# ProProject_my_heart_2023-08-05.net
KiCad netlist of a schematic drawn in EasyEDA Pro
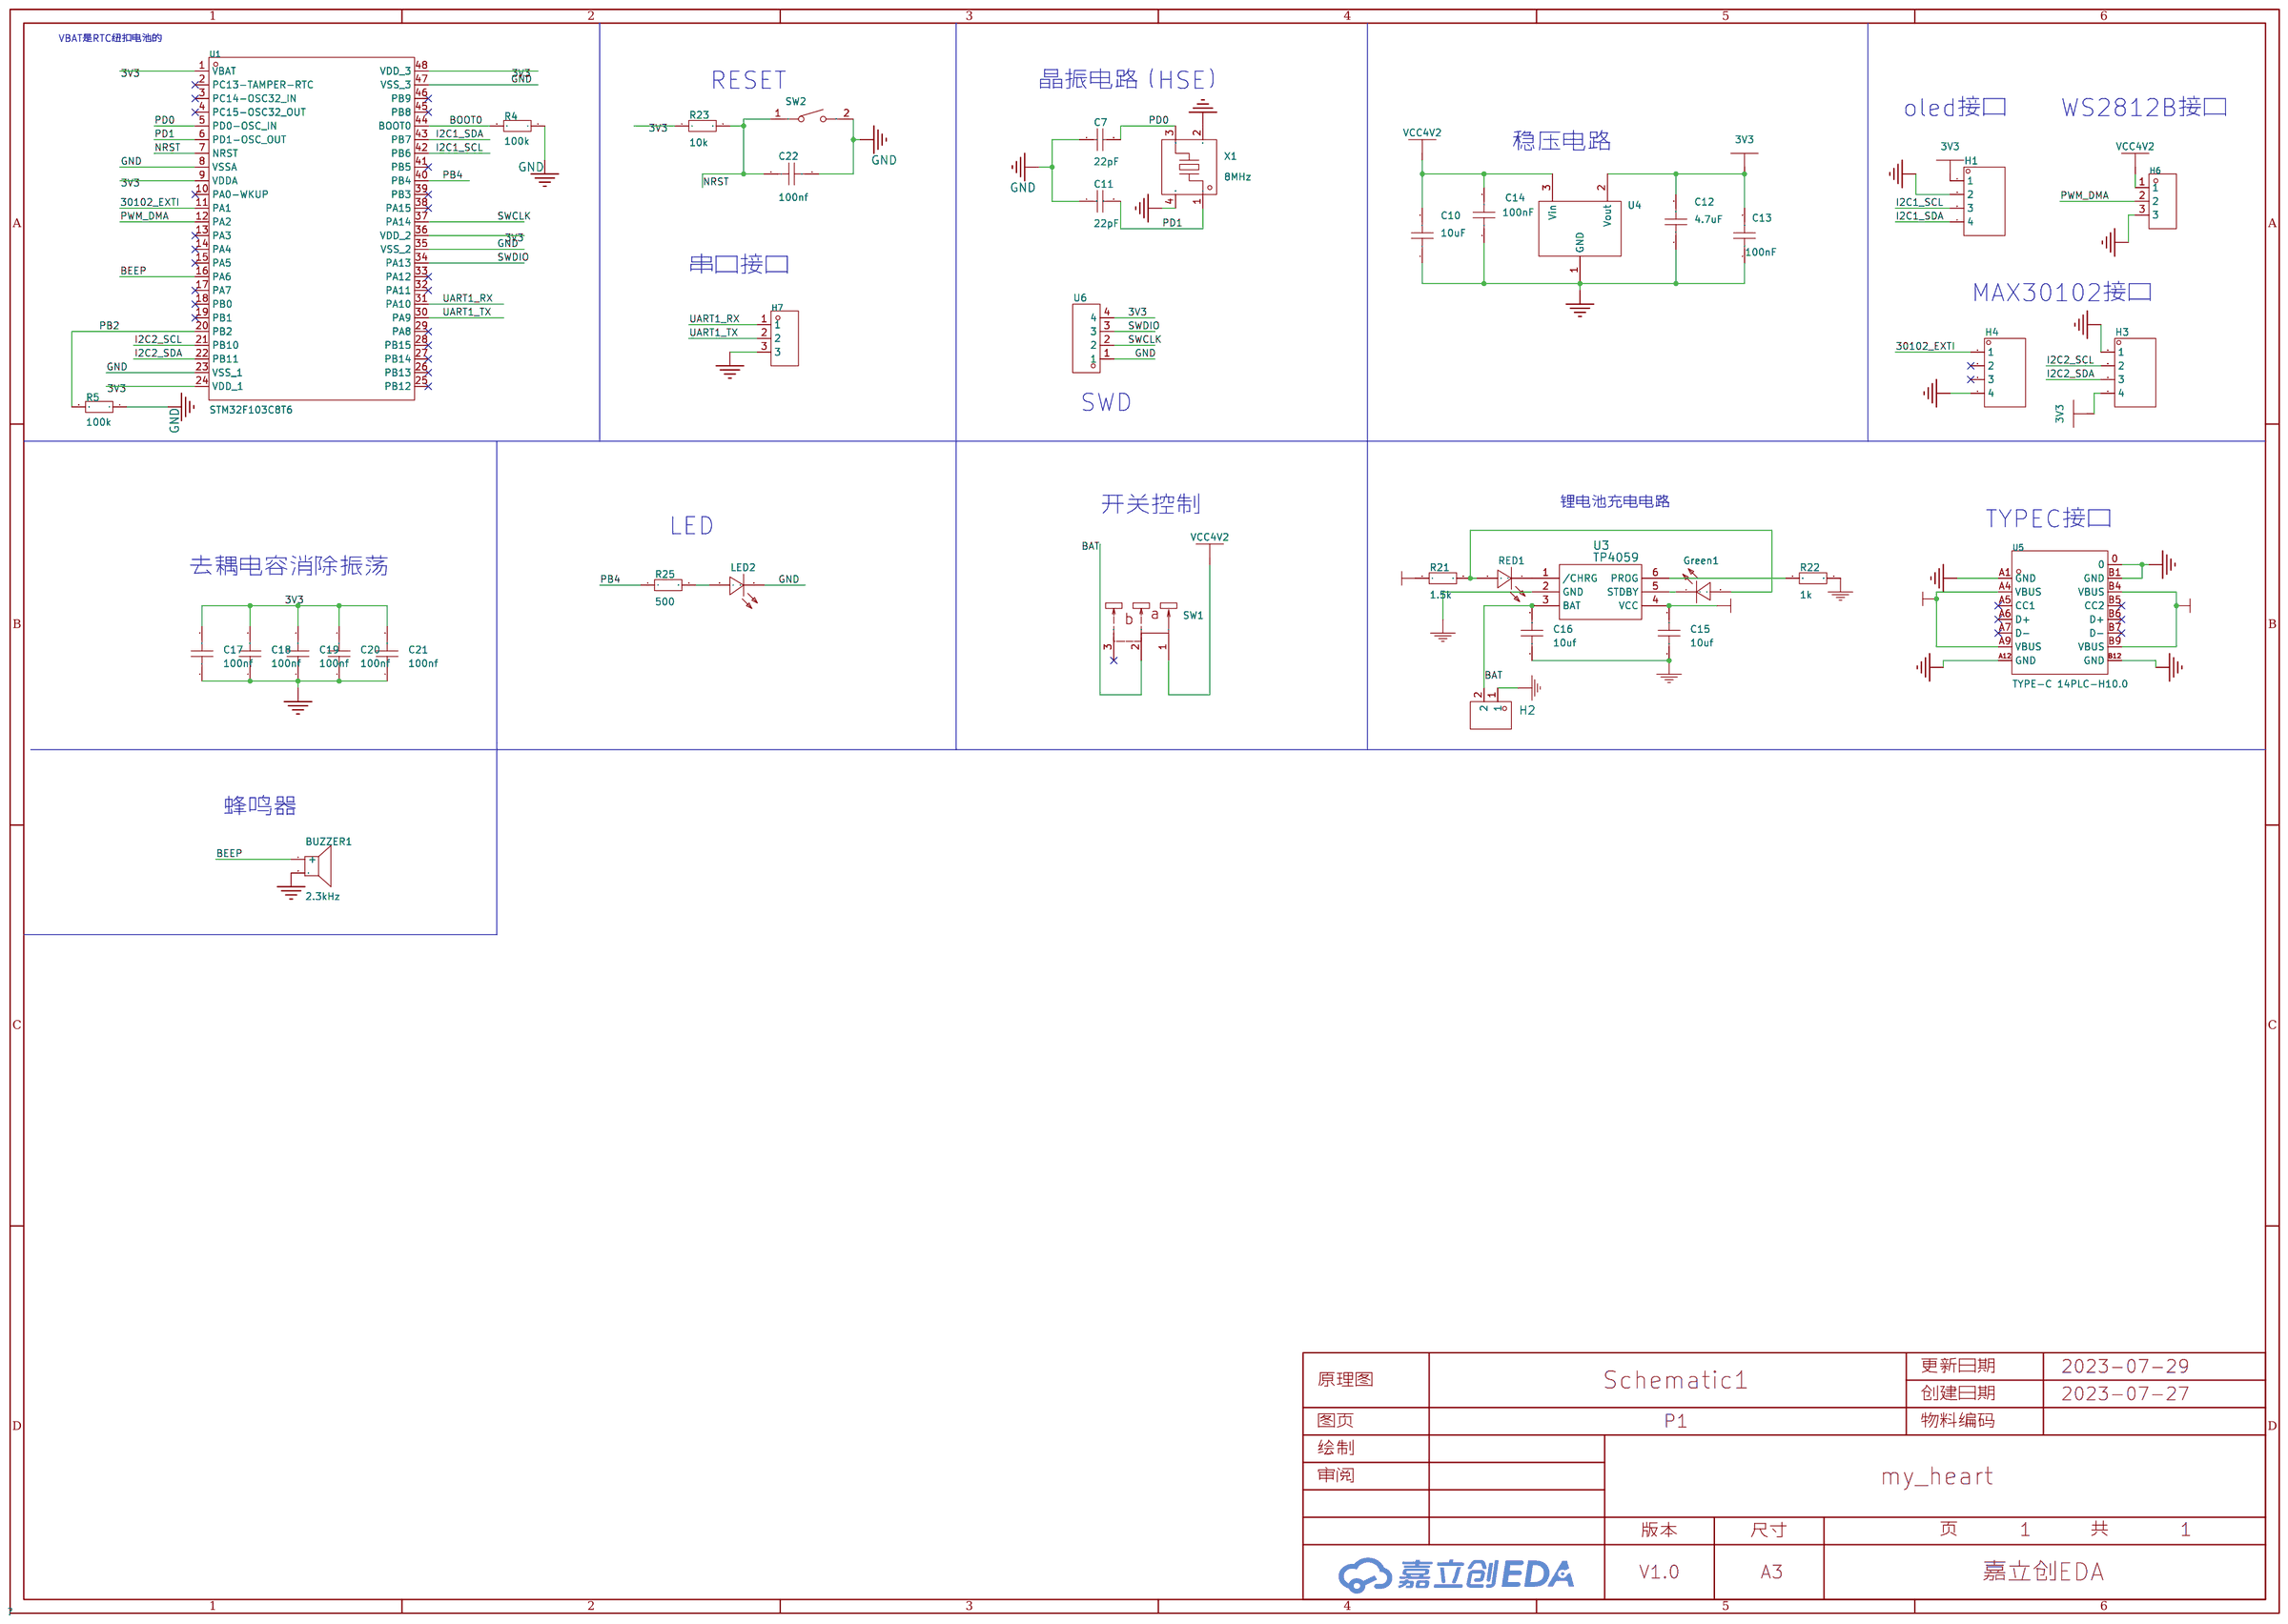
[diagram p0: schematic sheet]

(export (version "E")
  (design (tool "Eeschema 10.0.6"))
  (components
    (comp (ref "BUZZER1")
      (value "2.3kHz")
      (footprint "easyedapro:BUZ-TH_BD12.0-P7.60-D0.6-FD")
      (description "驱动方式:有源(内含驱动线路);构造类型:电磁式;额定电压:5V;频率:2.3kHz;声压(SPL):85dB@5V,10cm;")
      (fields (field (name "Manufacturer Part") "TMB12A05") (field (name "Manufacturer") "华能"))
      (libsource (lib "easyedapro") (part "TMB12A05"))
    )
    (comp (ref "C7")
      (value "22pF")
      (footprint "easyedapro:C0805")
      (description "容值:22pF;精度:±5%;额定电压:50V;温度系数:NP0;")
      (fields
        (field (name "Manufacturer Part") "CC0805JRNPO9BN220")
        (field (name "Manufacturer") "YAGEO(国巨)")
      )
      (libsource (lib "easyedapro") (part "CC0805JRNPO9BN220"))
    )
    (comp (ref "C10")
      (value "10uF")
      (footprint "easyedapro:c0805")
      (description "容值:10uF;精度:±10%;额定电压:16V;温度系数:X7R;")
      (fields
        (field (name "Manufacturer Part") "CL21B106KOQNNNE")
        (field (name "Manufacturer") "SAMSUNG(三星)")
      )
      (libsource (lib "easyedapro") (part "CL21B106KOQNNNE"))
    )
    (comp (ref "C11")
      (value "22pF")
      (footprint "easyedapro:C0805")
      (description "容值:22pF;精度:±5%;额定电压:50V;温度系数:NP0;")
      (fields
        (field (name "Manufacturer Part") "CC0805JRNPO9BN220")
        (field (name "Manufacturer") "YAGEO(国巨)")
      )
      (libsource (lib "easyedapro") (part "CC0805JRNPO9BN220"))
    )
    (comp (ref "C12")
      (value "4.7uF")
      (footprint "easyedapro:c0805")
      (description "容值:4.7uF;精度:±10%;额定电压:25V;温度系数:X5R;")
      (fields
        (field (name "Manufacturer Part") "CC0805KKX5R8BB475")
        (field (name "Manufacturer") "YAGEO(国巨)")
      )
      (libsource (lib "easyedapro") (part "CC0805KKX5R8BB475"))
    )
    (comp (ref "C13")
      (value "100nF")
      (footprint "easyedapro:c0805")
      (description "容值:100nF;精度:±10%;额定电压:25V;温度系数:X7R;")
      (fields
        (field (name "Manufacturer Part") "TCC0805X7R104K250DTS")
        (field (name "Manufacturer") "CCTC(三环)")
      )
      (libsource (lib "easyedapro") (part "TCC0805X7R104K250DTS"))
    )
    (comp (ref "C14")
      (value "100nF")
      (footprint "easyedapro:c0805")
      (description "容值:100nF;精度:±10%;额定电压:25V;温度系数:X7R;")
      (fields
        (field (name "Manufacturer Part") "TCC0805X7R104K250DTS")
        (field (name "Manufacturer") "CCTC(三环)")
      )
      (libsource (lib "easyedapro") (part "TCC0805X7R104K250DTS"))
    )
    (comp (ref "C15")
      (value "100nF")
      (footprint "easyedapro:C0603")
      (libsource (lib "easyedapro") (part "CapAcitance"))
    )
    (comp (ref "C16")
      (value "100nF")
      (footprint "easyedapro:C0603")
      (libsource (lib "easyedapro") (part "CapAcitance"))
    )
    (comp (ref "C17")
      (value "100nF")
      (footprint "easyedapro:C0603")
      (libsource (lib "easyedapro") (part "CapAcitance"))
    )
    (comp (ref "C18")
      (value "100nF")
      (footprint "easyedapro:C0603")
      (libsource (lib "easyedapro") (part "CapAcitance"))
    )
    (comp (ref "C19")
      (value "100nF")
      (footprint "easyedapro:C0603")
      (libsource (lib "easyedapro") (part "CapAcitance"))
    )
    (comp (ref "C20")
      (value "100nF")
      (footprint "easyedapro:C0603")
      (libsource (lib "easyedapro") (part "CapAcitance"))
    )
    (comp (ref "C21")
      (value "100nF")
      (footprint "easyedapro:C0603")
      (libsource (lib "easyedapro") (part "CapAcitance"))
    )
    (comp (ref "C22")
      (value "100nF")
      (footprint "easyedapro:C0603")
      (libsource (lib "easyedapro") (part "CapAcitance"))
    )
    (comp (ref "Green1")
      (value "KT-0603R")
      (footprint "easyedapro:LED0603-RD")
      (description "发光颜色:红灯;二极管配置:-;透镜颜色:-;主波长:-;色温:-;功率:-;发光角度:-;安装方式:-;工作温度:-40°C~+85°C;")
      (fields (field (name "Manufacturer") "KENTO"))
      (libsource (lib "easyedapro") (part "KT-0603R"))
    )
    (comp (ref "H1")
      (value "~")
      (footprint "easyedapro:HDR-TH_4P-P2.54-V-M_1")
      (fields (field (name "Manufacturer Part") "B-2100S04P-A110") (field (name "Manufacturer") "Ckmtw(灿科盟)"))
      (libsource (lib "easyedapro") (part "Header-Male-2.54_1x4"))
    )
    (comp (ref "H2")
      (value "MF254V-11-02-0743")
      (footprint "easyedapro:HDR-TH_2P-P2.00-V-M")
      (fields (field (name "Manufacturer") "XFCN(台湾兴飞)"))
      (libsource (lib "easyedapro") (part "MF254V-11-02-0743"))
    )
    (comp (ref "H3")
      (value "~")
      (footprint "easyedapro:HDR-TH_4P-P2.54-V-M_1")
      (fields (field (name "Manufacturer Part") "B-2100S04P-A110") (field (name "Manufacturer") "Ckmtw(灿科盟)"))
      (libsource (lib "easyedapro") (part "Header-Male-2.54_1x4"))
    )
    (comp (ref "H4")
      (value "~")
      (footprint "easyedapro:HDR-TH_4P-P2.54-V-M_1")
      (fields (field (name "Manufacturer Part") "B-2100S04P-A110") (field (name "Manufacturer") "Ckmtw(灿科盟)"))
      (libsource (lib "easyedapro") (part "Header-Male-2.54_1x4"))
    )
    (comp (ref "H6")
      (value "~")
      (footprint "easyedapro:HDR-TH_3P-P2.54-V-F")
      (libsource (lib "easyedapro") (part "PM254V-11-03-H85"))
    )
    (comp (ref "H7")
      (value "~")
      (footprint "easyedapro:HDR-TH_3P-P2.54-V-F")
      (libsource (lib "easyedapro") (part "PM254V-11-03-H85"))
    )
    (comp (ref "LED2")
      (value "KT-0603R")
      (footprint "easyedapro:LED0603-RD")
      (description "发光颜色:红灯;二极管配置:-;透镜颜色:-;主波长:-;色温:-;功率:-;发光角度:-;安装方式:-;工作温度:-40°C~+85°C;")
      (fields (field (name "Manufacturer") "KENTO"))
      (libsource (lib "easyedapro") (part "KT-0603R"))
    )
    (comp (ref "R4")
      (value "100k")
      (footprint "easyedapro:R0201")
      (description "阻值:10k;精度:±1%;功率:50mW;温度系数:±200ppm/;最大工作电压:25V;工作温度范围:-55~+125;")
      (fields (field (name "Manufacturer Part") "RC-01W1002FT") (field (name "Manufacturer") "FH(风华)"))
      (libsource (lib "easyedapro") (part "RC-01W1002FT"))
    )
    (comp (ref "R5")
      (value "100k")
      (footprint "easyedapro:R0201")
      (description "阻值:10k;精度:±1%;功率:50mW;温度系数:±200ppm/;最大工作电压:25V;工作温度范围:-55~+125;")
      (fields (field (name "Manufacturer Part") "RC-01W1002FT") (field (name "Manufacturer") "FH(风华)"))
      (libsource (lib "easyedapro") (part "RC-01W1002FT"))
    )
    (comp (ref "R21") (value "10K") (footprint "easyedapro:R0603") (libsource (lib "easyedapro") (part "电阻")))
    (comp (ref "R22") (value "10K") (footprint "easyedapro:R0603") (libsource (lib "easyedapro") (part "电阻")))
    (comp (ref "R23") (value "10K") (footprint "easyedapro:R0603") (libsource (lib "easyedapro") (part "电阻")))
    (comp (ref "R25") (value "10K") (footprint "easyedapro:R0603") (libsource (lib "easyedapro") (part "电阻")))
    (comp (ref "RED1")
      (value "KT-0603R")
      (footprint "easyedapro:LED0603-RD")
      (description "发光颜色:红灯;二极管配置:-;透镜颜色:-;主波长:-;色温:-;功率:-;发光角度:-;安装方式:-;工作温度:-40°C~+85°C;")
      (fields (field (name "Manufacturer") "KENTO"))
      (libsource (lib "easyedapro") (part "KT-0603R"))
    )
    (comp (ref "SW1")
      (value "~")
      (footprint "easyedapro:SW-TH_K3-1260D-K1")
      (fields (field (name "Manufacturer Part") "K3-1260D-K1") (field (name "Manufacturer") "韩国韩荣"))
      (libsource (lib "easyedapro") (part "K3-1260D-K1"))
    )
    (comp (ref "SW2")
      (value "TS-1088-AR02016")
      (footprint "easyedapro:SW-SMD_L3.9-W3.0-P4.45")
      (description "触点电流:50mA;额定电压(DC):12V;绝缘电阻:100MΩ;电路结构:单刀单掷;安装方式:立贴;作用力:160gf@±50gf;机械寿命:10万次;带支架:否;")
      (fields (field (name "Manufacturer") "XUNPU(讯普)"))
      (libsource (lib "easyedapro") (part "TS-1088-AR02016"))
    )
    (comp (ref "U1")
      (value "STM32F103C8T6")
      (footprint "easyedapro:LQFP-48_L7.0-W7.0-P0.50-LS9.0-BL")
      (fields (field (name "Manufacturer") "ST(意法半导体)"))
      (libsource (lib "easyedapro") (part "STM32F103C8T6"))
    )
    (comp (ref "U3")
      (value "TP4059")
      (footprint "easyedapro:SOT-23-6_L2.9-W1.6-P0.95-LS2.8-BR")
      (fields (field (name "Manufacturer") "TOPPOWER"))
      (libsource (lib "easyedapro") (part "TP4059"))
    )
    (comp (ref "U4")
      (value "~")
      (footprint "easyedapro:SOT-89-3_L4.5-W2.5-P1.50-LS4.2-BR")
      (description "输出类型:固定;输出极性:正;输出通道数:1;最大输入电压:15V;输出电压:3.3V;压差:1.3V@(1A);输出电流:1A;电源纹波抑制比(PRSS):75dB@(120Hz);")
      (fields (field (name "Manufacturer Part") "CJA1117B-3.3") (field (name "Manufacturer") "CJ（江苏长电/长晶）"))
      (libsource (lib "easyedapro") (part "CJA1117B-3.3"))
    )
    (comp (ref "U5")
      (value "TYPE-C 14PLC-H10.0")
      (footprint "easyedapro:USB-C-TH_SHOUHAN_TYPE-C-14PLC-H10.0")
      (description "连接器类型:Type-C;标准:-;公母:母座;触点数量:14P;端口数量:1;安装方式:立插;额定电流 - 电源:5A;触头材质:-;触头镀层:-;工作温度范围:-40°C~+85°C;")
      (fields (field (name "Manufacturer") "SHOU HAN(首韩)"))
      (libsource (lib "easyedapro") (part "TYPE-C 14PLC-H10.0"))
    )
    (comp (ref "U6")
      (value "~")
      (footprint "easyedapro:HDR-TH_4P-P2.54-V-M-3")
      (fields (field (name "Manufacturer Part") "SIP4"))
      (libsource (lib "easyedapro") (part "SIP4"))
    )
    (comp (ref "X1")
      (value "8MHz")
      (footprint "easyedapro:OSC-SMD_4P-L3.2-W2.5-BL")
      (description "频率:8MHz;频率公差:±10ppm;负载电容:12pF;")
      (fields (field (name "Manufacturer Part") "X32258MOB4SI") (field (name "Manufacturer") "YXC(扬兴晶振)"))
      (libsource (lib "easyedapro") (part "X32258MOB4SI"))
    )
  )
  (nets
    (net (code "1") (name "/30102_EXTI") (class "Default")
      (node (ref "H4") (pin "1") (pinfunction "1_1") (pintype "input"))
      (node (ref "U1") (pin "11") (pinfunction "PA1_11") (pintype "input"))
    )
    (net (code "2") (name "/BAT") (class "Default")
      (node (ref "C16") (pin "2") (pinfunction "2_2") (pintype "input"))
      (node (ref "H2") (pin "2") (pinfunction "2_2") (pintype "input"))
      (node (ref "SW1") (pin "2") (pinfunction "2_2") (pintype "input"))
      (node (ref "U3") (pin "3") (pinfunction "BAT_3") (pintype "input"))
    )
    (net (code "3") (name "/BEEP") (class "Default")
      (node (ref "BUZZER1") (pin "1") (pinfunction "+_1") (pintype "input"))
      (node (ref "U1") (pin "16") (pinfunction "PA6_16") (pintype "input"))
    )
    (net (code "4") (name "/BOOT0") (class "Default")
      (node (ref "R4") (pin "2") (pinfunction "2_2") (pintype "input"))
      (node (ref "U1") (pin "44") (pinfunction "BOOT0_44") (pintype "input"))
    )
    (net (code "5") (name "/I2C1_SCL") (class "Default")
      (node (ref "H1") (pin "3") (pinfunction "3_3") (pintype "input"))
      (node (ref "U1") (pin "42") (pinfunction "PB6_42") (pintype "input"))
    )
    (net (code "6") (name "/I2C1_SDA") (class "Default")
      (node (ref "H1") (pin "4") (pinfunction "4_4") (pintype "input"))
      (node (ref "U1") (pin "43") (pinfunction "PB7_43") (pintype "input"))
    )
    (net (code "7") (name "/I2C2_SCL") (class "Default")
      (node (ref "H3") (pin "2") (pinfunction "2_2") (pintype "input"))
      (node (ref "U1") (pin "21") (pinfunction "PB10_21") (pintype "input"))
    )
    (net (code "8") (name "/I2C2_SDA") (class "Default")
      (node (ref "H3") (pin "3") (pinfunction "3_3") (pintype "input"))
      (node (ref "U1") (pin "22") (pinfunction "PB11_22") (pintype "input"))
    )
    (net (code "9") (name "/NRST") (class "Default")
      (node (ref "C22") (pin "2") (pinfunction "2_2") (pintype "input"))
      (node (ref "R23") (pin "2") (pinfunction "2_2") (pintype "input"))
      (node (ref "SW2") (pin "1") (pinfunction "1_1") (pintype "input"))
      (node (ref "U1") (pin "7") (pinfunction "NRST_7") (pintype "input"))
    )
    (net (code "10") (name "/PB2") (class "Default")
      (node (ref "R5") (pin "2") (pinfunction "2_2") (pintype "input"))
      (node (ref "U1") (pin "20") (pinfunction "PB2_20") (pintype "input"))
    )
    (net (code "11") (name "/PB4") (class "Default")
      (node (ref "R25") (pin "1") (pinfunction "1_1") (pintype "input"))
      (node (ref "U1") (pin "40") (pinfunction "PB4_40") (pintype "input"))
    )
    (net (code "12") (name "/PD0") (class "Default")
      (node (ref "C7") (pin "2") (pinfunction "2_2") (pintype "input"))
      (node (ref "U1") (pin "5") (pinfunction "PD0-OSC_IN_5") (pintype "input"))
      (node (ref "X1") (pin "3") (pinfunction "3_3") (pintype "input"))
    )
    (net (code "13") (name "/PD1") (class "Default")
      (node (ref "C11") (pin "2") (pinfunction "2_2") (pintype "input"))
      (node (ref "U1") (pin "6") (pinfunction "PD1-OSC_OUT_6") (pintype "input"))
      (node (ref "X1") (pin "1") (pinfunction "1_1") (pintype "input"))
    )
    (net (code "14") (name "/PWM_DMA") (class "Default")
      (node (ref "H6") (pin "2") (pinfunction "2_2") (pintype "input"))
      (node (ref "U1") (pin "12") (pinfunction "PA2_12") (pintype "input"))
    )
    (net (code "15") (name "/SWCLK") (class "Default")
      (node (ref "U1") (pin "37") (pinfunction "PA14_37") (pintype "input"))
      (node (ref "U6") (pin "2") (pinfunction "2_2") (pintype "input"))
    )
    (net (code "16") (name "/SWDIO") (class "Default")
      (node (ref "U1") (pin "34") (pinfunction "PA13_34") (pintype "input"))
      (node (ref "U6") (pin "3") (pinfunction "3_3") (pintype "input"))
    )
    (net (code "17") (name "/UART1_RX") (class "Default")
      (node (ref "H7") (pin "1") (pinfunction "1_1") (pintype "input"))
      (node (ref "U1") (pin "31") (pinfunction "PA10_31") (pintype "input"))
    )
    (net (code "18") (name "/UART1_TX") (class "Default")
      (node (ref "H7") (pin "2") (pinfunction "2_2") (pintype "input"))
      (node (ref "U1") (pin "30") (pinfunction "PA9_30") (pintype "input"))
    )
    (net (code "19") (name "3V3") (class "Default")
      (node (ref "C12") (pin "2") (pinfunction "2_2") (pintype "input"))
      (node (ref "C13") (pin "2") (pinfunction "2_2") (pintype "input"))
      (node (ref "C17") (pin "2") (pinfunction "2_2") (pintype "input"))
      (node (ref "C18") (pin "2") (pinfunction "2_2") (pintype "input"))
      (node (ref "C19") (pin "2") (pinfunction "2_2") (pintype "input"))
      (node (ref "C20") (pin "2") (pinfunction "2_2") (pintype "input"))
      (node (ref "C21") (pin "2") (pinfunction "2_2") (pintype "input"))
      (node (ref "H1") (pin "1") (pinfunction "1_1") (pintype "input"))
      (node (ref "H3") (pin "4") (pinfunction "4_4") (pintype "input"))
      (node (ref "R23") (pin "1") (pinfunction "1_1") (pintype "input"))
      (node (ref "U1") (pin "1") (pinfunction "VBAT_1") (pintype "input"))
      (node (ref "U1") (pin "24") (pinfunction "VDD_1_24") (pintype "input"))
      (node (ref "U1") (pin "36") (pinfunction "VDD_2_36") (pintype "input"))
      (node (ref "U1") (pin "48") (pinfunction "VDD_3_48") (pintype "input"))
      (node (ref "U1") (pin "9") (pinfunction "VDDA_9") (pintype "input"))
      (node (ref "U4") (pin "2") (pinfunction "Vout_2") (pintype "input"))
      (node (ref "U6") (pin "4") (pinfunction "4_4") (pintype "input"))
    )
    (net (code "20") (name "GND") (class "Default")
      (node (ref "BUZZER1") (pin "2") (pinfunction "2_2") (pintype "input"))
      (node (ref "C10") (pin "1") (pinfunction "1_1") (pintype "input"))
      (node (ref "C11") (pin "1") (pinfunction "1_1") (pintype "input"))
      (node (ref "C12") (pin "1") (pinfunction "1_1") (pintype "input"))
      (node (ref "C13") (pin "1") (pinfunction "1_1") (pintype "input"))
      (node (ref "C14") (pin "1") (pinfunction "1_1") (pintype "input"))
      (node (ref "C15") (pin "1") (pinfunction "1_1") (pintype "input"))
      (node (ref "C16") (pin "1") (pinfunction "1_1") (pintype "input"))
      (node (ref "C17") (pin "1") (pinfunction "1_1") (pintype "input"))
      (node (ref "C18") (pin "1") (pinfunction "1_1") (pintype "input"))
      (node (ref "C19") (pin "1") (pinfunction "1_1") (pintype "input"))
      (node (ref "C20") (pin "1") (pinfunction "1_1") (pintype "input"))
      (node (ref "C21") (pin "1") (pinfunction "1_1") (pintype "input"))
      (node (ref "C22") (pin "1") (pinfunction "1_1") (pintype "input"))
      (node (ref "C7") (pin "1") (pinfunction "1_1") (pintype "input"))
      (node (ref "H1") (pin "2") (pinfunction "2_2") (pintype "input"))
      (node (ref "H2") (pin "1") (pinfunction "1_1") (pintype "input"))
      (node (ref "H3") (pin "1") (pinfunction "1_1") (pintype "input"))
      (node (ref "H4") (pin "4") (pinfunction "4_4") (pintype "input"))
      (node (ref "H6") (pin "3") (pinfunction "3_3") (pintype "input"))
      (node (ref "H7") (pin "3") (pinfunction "3_3") (pintype "input"))
      (node (ref "LED2") (pin "1") (pinfunction "K_1") (pintype "input"))
      (node (ref "R22") (pin "2") (pinfunction "2_2") (pintype "input"))
      (node (ref "R4") (pin "1") (pinfunction "1_1") (pintype "input"))
      (node (ref "R5") (pin "1") (pinfunction "1_1") (pintype "input"))
      (node (ref "SW2") (pin "2") (pinfunction "2_2") (pintype "input"))
      (node (ref "U1") (pin "23") (pinfunction "VSS_1_23") (pintype "input"))
      (node (ref "U1") (pin "35") (pinfunction "VSS_2_35") (pintype "input"))
      (node (ref "U1") (pin "47") (pinfunction "VSS_3_47") (pintype "input"))
      (node (ref "U1") (pin "8") (pinfunction "VSSA_8") (pintype "input"))
      (node (ref "U3") (pin "2") (pinfunction "GND_2") (pintype "input"))
      (node (ref "U4") (pin "1") (pinfunction "GND_1") (pintype "input"))
      (node (ref "U5") (pin "0") (pinfunction "0_0") (pintype "input"))
      (node (ref "U5") (pin "A1") (pinfunction "GND_A1") (pintype "input"))
      (node (ref "U5") (pin "A12") (pinfunction "GND_A12") (pintype "input"))
      (node (ref "U5") (pin "B1") (pinfunction "GND_B1") (pintype "input"))
      (node (ref "U5") (pin "B12") (pinfunction "GND_B12") (pintype "input"))
      (node (ref "U6") (pin "1") (pinfunction "1_1") (pintype "input"))
      (node (ref "X1") (pin "2") (pinfunction "GND_2") (pintype "input"))
      (node (ref "X1") (pin "4") (pinfunction "GND_4") (pintype "input"))
    )
    (net (code "21") (name "Net-(Green1-A)") (class "Default")
      (node (ref "Green1") (pin "2") (pinfunction "A_2") (pintype "input"))
      (node (ref "R21") (pin "2") (pinfunction "2_2") (pintype "input"))
      (node (ref "RED1") (pin "2") (pinfunction "A_2") (pintype "input"))
    )
    (net (code "22") (name "Net-(Green1-K)") (class "Default")
      (node (ref "Green1") (pin "1") (pinfunction "K_1") (pintype "input"))
      (node (ref "U3") (pin "5") (pinfunction "STDBY_5") (pintype "input"))
    )
    (net (code "23") (name "Net-(LED2-A)") (class "Default")
      (node (ref "LED2") (pin "2") (pinfunction "A_2") (pintype "input"))
      (node (ref "R25") (pin "2") (pinfunction "2_2") (pintype "input"))
    )
    (net (code "24") (name "Net-(RED1-K)") (class "Default")
      (node (ref "RED1") (pin "1") (pinfunction "K_1") (pintype "input"))
      (node (ref "U3") (pin "1") (pinfunction "/CHRG_1") (pintype "input"))
    )
    (net (code "25") (name "Net-(U3-PROG)") (class "Default")
      (node (ref "R22") (pin "1") (pinfunction "1_1") (pintype "input"))
      (node (ref "U3") (pin "6") (pinfunction "PROG_6") (pintype "input"))
    )
    (net (code "26") (name "VCC4V2") (class "Default")
      (node (ref "C10") (pin "2") (pinfunction "2_2") (pintype "input"))
      (node (ref "C14") (pin "2") (pinfunction "2_2") (pintype "input"))
      (node (ref "H6") (pin "1") (pinfunction "1_1") (pintype "input"))
      (node (ref "SW1") (pin "1") (pinfunction "1_1") (pintype "input"))
      (node (ref "U4") (pin "3") (pinfunction "Vin_3") (pintype "input"))
    )
    (net (code "27") (name "VCC5V") (class "Default")
      (node (ref "C15") (pin "2") (pinfunction "2_2") (pintype "input"))
      (node (ref "R21") (pin "1") (pinfunction "1_1") (pintype "input"))
      (node (ref "U3") (pin "4") (pinfunction "VCC_4") (pintype "input"))
      (node (ref "U5") (pin "A4") (pinfunction "VBUS_A4") (pintype "input"))
      (node (ref "U5") (pin "A9") (pinfunction "VBUS_A9") (pintype "input"))
      (node (ref "U5") (pin "B4") (pinfunction "VBUS_B4") (pintype "input"))
      (node (ref "U5") (pin "B9") (pinfunction "VBUS_B9") (pintype "input"))
    )
    (net (code "28") (name "unconnected-(H4-Pad2)") (class "Default")
      (node (ref "H4") (pin "2") (pinfunction "2_2") (pintype "input+no_connect"))
    )
    (net (code "29") (name "unconnected-(H4-Pad3)") (class "Default")
      (node (ref "H4") (pin "3") (pinfunction "3_3") (pintype "input+no_connect"))
    )
    (net (code "30") (name "unconnected-(SW1-Pad3)") (class "Default")
      (node (ref "SW1") (pin "3") (pinfunction "3_3") (pintype "input+no_connect"))
    )
    (net (code "31") (name "unconnected-(U1-PA0-WKUP-Pad10)") (class "Default")
      (node (ref "U1") (pin "10") (pinfunction "PA0-WKUP_10") (pintype "input+no_connect"))
    )
    (net (code "32") (name "unconnected-(U1-PA3-Pad13)") (class "Default")
      (node (ref "U1") (pin "13") (pinfunction "PA3_13") (pintype "input+no_connect"))
    )
    (net (code "33") (name "unconnected-(U1-PA4-Pad14)") (class "Default")
      (node (ref "U1") (pin "14") (pinfunction "PA4_14") (pintype "input+no_connect"))
    )
    (net (code "34") (name "unconnected-(U1-PA5-Pad15)") (class "Default")
      (node (ref "U1") (pin "15") (pinfunction "PA5_15") (pintype "input+no_connect"))
    )
    (net (code "35") (name "unconnected-(U1-PA7-Pad17)") (class "Default")
      (node (ref "U1") (pin "17") (pinfunction "PA7_17") (pintype "input+no_connect"))
    )
    (net (code "36") (name "unconnected-(U1-PA8-Pad29)") (class "Default")
      (node (ref "U1") (pin "29") (pinfunction "PA8_29") (pintype "input+no_connect"))
    )
    (net (code "37") (name "unconnected-(U1-PA11-Pad32)") (class "Default")
      (node (ref "U1") (pin "32") (pinfunction "PA11_32") (pintype "input+no_connect"))
    )
    (net (code "38") (name "unconnected-(U1-PA12-Pad33)") (class "Default")
      (node (ref "U1") (pin "33") (pinfunction "PA12_33") (pintype "input+no_connect"))
    )
    (net (code "39") (name "unconnected-(U1-PA15-Pad38)") (class "Default")
      (node (ref "U1") (pin "38") (pinfunction "PA15_38") (pintype "input+no_connect"))
    )
    (net (code "40") (name "unconnected-(U1-PB0-Pad18)") (class "Default")
      (node (ref "U1") (pin "18") (pinfunction "PB0_18") (pintype "input+no_connect"))
    )
    (net (code "41") (name "unconnected-(U1-PB1-Pad19)") (class "Default")
      (node (ref "U1") (pin "19") (pinfunction "PB1_19") (pintype "input+no_connect"))
    )
    (net (code "42") (name "unconnected-(U1-PB3-Pad39)") (class "Default")
      (node (ref "U1") (pin "39") (pinfunction "PB3_39") (pintype "input+no_connect"))
    )
    (net (code "43") (name "unconnected-(U1-PB5-Pad41)") (class "Default")
      (node (ref "U1") (pin "41") (pinfunction "PB5_41") (pintype "input+no_connect"))
    )
    (net (code "44") (name "unconnected-(U1-PB8-Pad45)") (class "Default")
      (node (ref "U1") (pin "45") (pinfunction "PB8_45") (pintype "input+no_connect"))
    )
    (net (code "45") (name "unconnected-(U1-PB9-Pad46)") (class "Default")
      (node (ref "U1") (pin "46") (pinfunction "PB9_46") (pintype "input+no_connect"))
    )
    (net (code "46") (name "unconnected-(U1-PB12-Pad25)") (class "Default")
      (node (ref "U1") (pin "25") (pinfunction "PB12_25") (pintype "input+no_connect"))
    )
    (net (code "47") (name "unconnected-(U1-PB13-Pad26)") (class "Default")
      (node (ref "U1") (pin "26") (pinfunction "PB13_26") (pintype "input+no_connect"))
    )
    (net (code "48") (name "unconnected-(U1-PB14-Pad27)") (class "Default")
      (node (ref "U1") (pin "27") (pinfunction "PB14_27") (pintype "input+no_connect"))
    )
    (net (code "49") (name "unconnected-(U1-PB15-Pad28)") (class "Default")
      (node (ref "U1") (pin "28") (pinfunction "PB15_28") (pintype "input+no_connect"))
    )
    (net (code "50") (name "unconnected-(U1-PC13-TAMPER-RTC-Pad2)") (class "Default")
      (node (ref "U1") (pin "2") (pinfunction "PC13-TAMPER-RTC_2") (pintype "input+no_connect"))
    )
    (net (code "51") (name "unconnected-(U1-PC14-OSC32_IN-Pad3)") (class "Default")
      (node (ref "U1") (pin "3") (pinfunction "PC14-OSC32_IN_3") (pintype "input+no_connect"))
    )
    (net (code "52") (name "unconnected-(U1-PC15-OSC32_OUT-Pad4)") (class "Default")
      (node (ref "U1") (pin "4") (pinfunction "PC15-OSC32_OUT_4") (pintype "input+no_connect"))
    )
    (net (code "53") (name "unconnected-(U5-CC1-PadA5)") (class "Default")
      (node (ref "U5") (pin "A5") (pinfunction "CC1_A5") (pintype "input+no_connect"))
    )
    (net (code "54") (name "unconnected-(U5-CC2-PadB5)") (class "Default")
      (node (ref "U5") (pin "B5") (pinfunction "CC2_B5") (pintype "input+no_connect"))
    )
    (net (code "55") (name "unconnected-(U5-D+-PadA6)") (class "Default")
      (node (ref "U5") (pin "A6") (pinfunction "D+_A6") (pintype "input+no_connect"))
    )
    (net (code "56") (name "unconnected-(U5-D+-PadB6)") (class "Default")
      (node (ref "U5") (pin "B6") (pinfunction "D+_B6") (pintype "input+no_connect"))
    )
    (net (code "57") (name "unconnected-(U5-D--PadA7)") (class "Default")
      (node (ref "U5") (pin "A7") (pinfunction "D-_A7") (pintype "input+no_connect"))
    )
    (net (code "58") (name "unconnected-(U5-D--PadB7)") (class "Default")
      (node (ref "U5") (pin "B7") (pinfunction "D-_B7") (pintype "input+no_connect"))
    )
  )
)
